# PWR_Supply_With_BUCK_Converter.net
KiCad netlist of a schematic drawn in Altium Designer
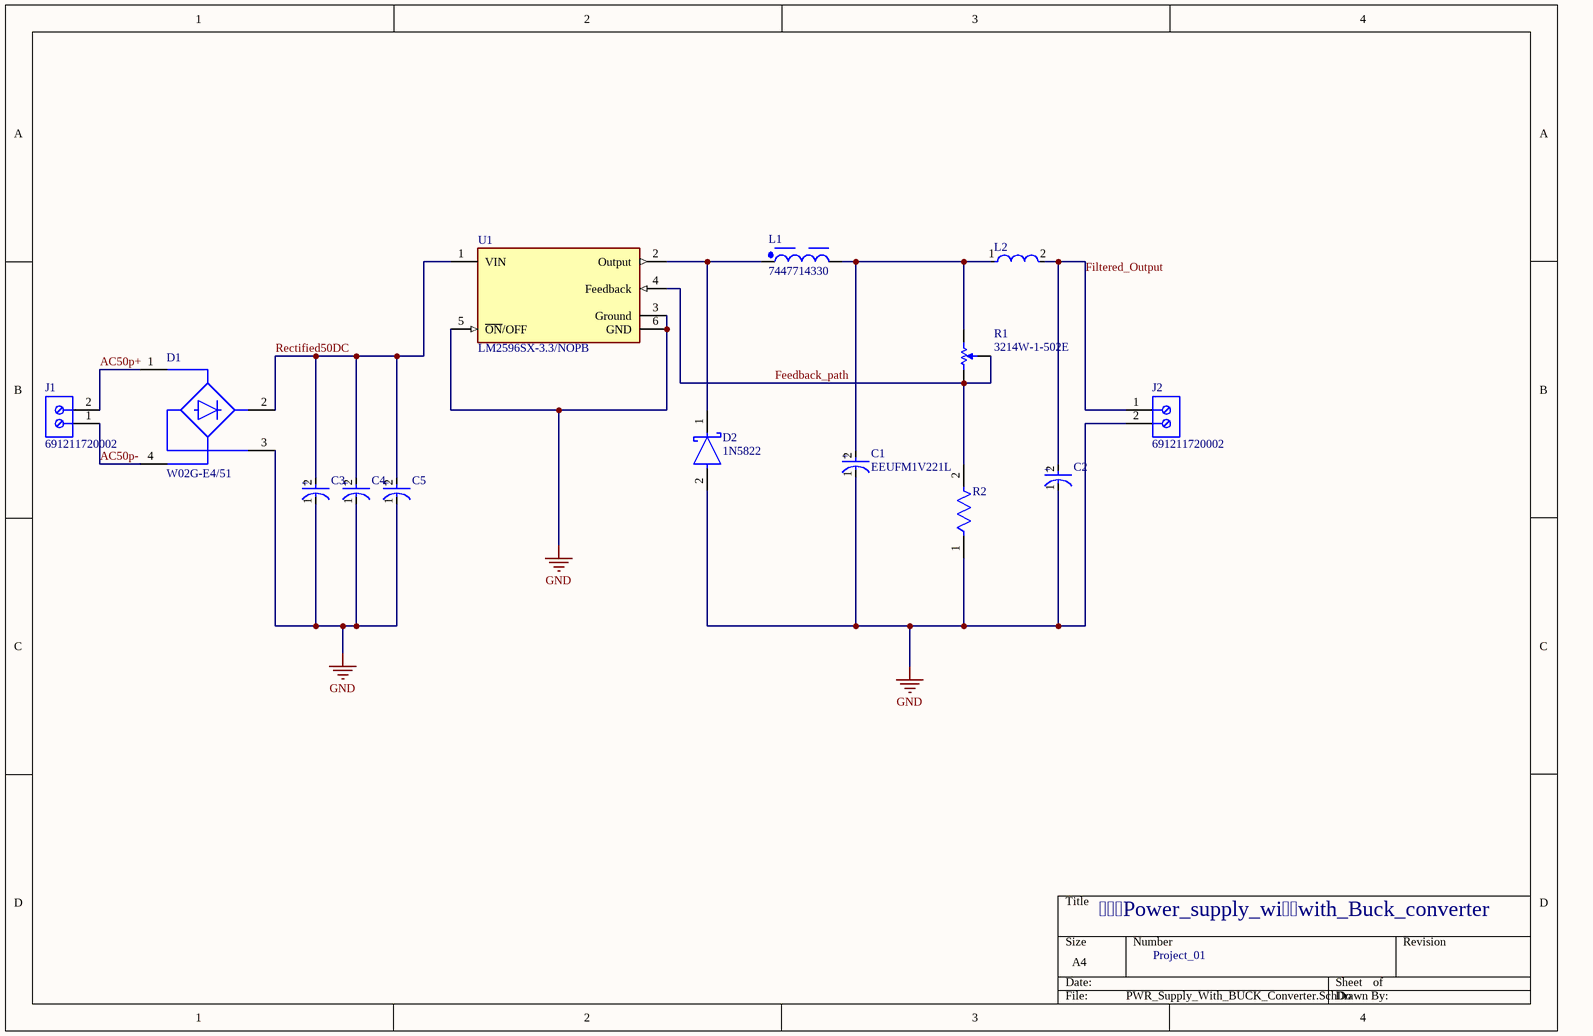
[diagram p0: PWR_Supply_With_BUCK_Converter.SchDoc]

(export (version "E")
  (design (tool "Eeschema 10.0.6"))
  (components
    (comp (ref "C1")
      (value "EEUFM1V221L")
      (footprint "FP-RAD-TH-D_8_0_5-L_15_1-MFG")
      (description "Aluminum Electrolytic Capacitors (Radial Lead Type) 220uF ±20% 35V")
      (fields (field (name "TOLERANCE") "20%") (field (name "VOLTAGE") "35V"))
      (libsource (lib "Altium Content Vault") (part "a00bbbee19879c290e62620ae7e47b1"))
    )
    (comp (ref "C2")
      (value "EEUFR1H101")
      (footprint "FP-RAD-TH-D_8_0_5-L_11_5-MFG")
      (description "Aluminum Electrolytic Capacitors (Radial Lead Type) 100uF ±20% 50V")
      (fields (field (name "VOLTAGE") "50V") (field (name "TOLERANCE") "20%"))
      (libsource (lib "Altium Content Vault") (part "a00bbbee19879c290e62620ae7e47b1"))
    )
    (comp (ref "C3")
      (value "EEUFK0J102L")
      (footprint "FP-RAD-TH-D_8_0_5-L_15_1-MFG")
      (description "Aluminum Electrolytic Capacitors (Radial Lead Type) AEC-Q200 Qualified 1000uF ±20% 6.3V")
      (fields (field (name "VOLTAGE") "6.3V") (field (name "TOLERANCE") "20%"))
      (libsource (lib "Altium Content Vault") (part "a00bbbee19879c290e62620ae7e47b1"))
    )
    (comp (ref "C4")
      (value "EEUFK0J102L")
      (footprint "FP-RAD-TH-D_8_0_5-L_15_1-MFG")
      (description "Aluminum Electrolytic Capacitors (Radial Lead Type) AEC-Q200 Qualified 1000uF ±20% 6.3V")
      (fields (field (name "VOLTAGE") "6.3V") (field (name "TOLERANCE") "20%"))
      (libsource (lib "Altium Content Vault") (part "a00bbbee19879c290e62620ae7e47b1"))
    )
    (comp (ref "C5")
      (value "EEUFR1H101")
      (footprint "FP-RAD-TH-D_8_0_5-L_11_5-MFG")
      (description "Aluminum Electrolytic Capacitors (Radial Lead Type) 100uF ±20% 50V")
      (fields (field (name "VOLTAGE") "50V") (field (name "TOLERANCE") "20%"))
      (libsource (lib "Altium Content Vault") (part "a00bbbee19879c290e62620ae7e47b1"))
    )
    (comp (ref "D1")
      (value "W02G-E4/51")
      (footprint "FP-WOG-MFG")
      (description "BRIDGE RECT 1PHASE 200V 1.5A WOG")
      (libsource (lib "Altium Content Vault") (part "ce9e859d166ef05ab3fd3217f7b9797"))
    )
    (comp (ref "D2")
      (value "1N5822")
      (footprint "FP-DO-201AD-MFG")
      (description "DIODE SCHOTTKY 40V 3A DO201AD")
      (fields
        (field (name "OCTOPART") "https://octopart.com/1n5822-stmicroelectronics-323225")
        (field (name "MANUFACTURER") "STMicroelectronics")
      )
      (libsource (lib "Altium Content Vault") (part "1d6ec82d83fb6aee721767c19dac4b9"))
    )
    (comp (ref "J1")
      (value "691211720002")
      (footprint "691211720002")
      (fields (field (name "VOLTAGE") "300V"))
      (libsource (lib "Altium Content Vault") (part "TBL - 1R - 02P - Screw"))
    )
    (comp (ref "J2")
      (value "691211720002")
      (footprint "691211720002")
      (fields (field (name "VOLTAGE") "300V"))
      (libsource (lib "Altium Content Vault") (part "TBL - 1R - 02P - Screw"))
    )
    (comp (ref "L1")
      (value "7447714330")
      (footprint "WE-PD_1050P")
      (fields (field (name "TOLERANCE") "20%"))
      (libsource (lib "Altium Content Vault") (part "Inductor - 2"))
    )
    (comp (ref "L2")
      (value "IHLP2525CZER220M11")
      (footprint "FP-IHLP-2525CZ-FP_2_413x3-MFG")
      (description "Commercial Inductors, Low DCR Series 22uH 2.9A 135mΩ 20%")
      (fields (field (name "TOLERANCE") "20%"))
      (libsource (lib "Altium Content Vault") (part "725321dda6339637d4d059423bc1c3c"))
    )
    (comp (ref "R1")
      (value "3214W-1-502E")
      (footprint "BOUR-3214W_V")
      (fields (field (name "MANUFACTURER") "Bourns"))
      (libsource (lib "Altium Content Vault") (part "RES-ADJ-3_A"))
    )
    (comp (ref "R2")
      (value "MCA12060D5000BP500")
      (footprint "FP-MCA1206-IPC_C")
      (description "Res MC Precision Thin Film 1206 500Ω 0.1% 0.25W ±25ppm/°C Molded Paper T/R")
      (fields (field (name "TOLERANCE") "0.1%"))
      (libsource (lib "Altium Content Vault") (part "1029c3af85768c4190bb7ad29bc67b5"))
    )
    (comp (ref "U1")
      (value "LM2596SX-3.3/NOPB")
      (footprint "FP-KTT0005B-MFG")
      (description "IC REG BUCK 3.3V 3A TO263-5")
      (libsource (lib "Altium Content Vault") (part "764e866748593119a4ee8b47c98b122"))
    )
  )
  (nets
    (net (code "1") (name "/AC50p+") (class "Default")
      (node (ref "D1") (pin "1") (pinfunction "1_~_1") (pintype "passive"))
      (node (ref "J1") (pin "2") (pinfunction "2_2") (pintype "passive"))
    )
    (net (code "2") (name "/AC50p-") (class "Default")
      (node (ref "D1") (pin "4") (pinfunction "2_~_4") (pintype "passive"))
      (node (ref "J1") (pin "1") (pinfunction "1_1") (pintype "passive"))
    )
    (net (code "3") (name "/Feedback_path") (class "Default")
      (node (ref "R1") (pin "1") (pinfunction "1_1") (pintype "passive"))
      (node (ref "R1") (pin "2") (pinfunction "2_2") (pintype "passive"))
      (node (ref "R2") (pin "2") (pinfunction "2_2") (pintype "passive"))
      (node (ref "U1") (pin "4") (pinfunction "Feedback_4") (pintype "input"))
    )
    (net (code "4") (name "/Filtered_Output") (class "Default")
      (node (ref "C2") (pin "2") (pinfunction "A_2") (pintype "passive"))
      (node (ref "J2") (pin "1") (pinfunction "1_1") (pintype "passive"))
      (node (ref "L2") (pin "2") (pinfunction "2_2") (pintype "passive"))
    )
    (net (code "5") (name "/Rectified50DC") (class "Default")
      (node (ref "C3") (pin "2") (pinfunction "A_2") (pintype "passive"))
      (node (ref "C4") (pin "2") (pinfunction "A_2") (pintype "passive"))
      (node (ref "C5") (pin "2") (pinfunction "A_2") (pintype "passive"))
      (node (ref "D1") (pin "2") (pinfunction "+_2") (pintype "passive"))
      (node (ref "U1") (pin "1") (pinfunction "VIN_1") (pintype "power_in"))
    )
    (net (code "6") (name "GND") (class "Default")
      (node (ref "C1") (pin "1") (pinfunction "C_1") (pintype "passive"))
      (node (ref "C2") (pin "1") (pinfunction "C_1") (pintype "passive"))
      (node (ref "C3") (pin "1") (pinfunction "C_1") (pintype "passive"))
      (node (ref "C4") (pin "1") (pinfunction "C_1") (pintype "passive"))
      (node (ref "C5") (pin "1") (pinfunction "C_1") (pintype "passive"))
      (node (ref "D1") (pin "3") (pinfunction "-_3") (pintype "passive"))
      (node (ref "D2") (pin "2") (pinfunction "A_2") (pintype "passive"))
      (node (ref "J2") (pin "2") (pinfunction "2_2") (pintype "passive"))
      (node (ref "R2") (pin "1") (pinfunction "1_1") (pintype "passive"))
      (node (ref "U1") (pin "3") (pinfunction "Ground_3") (pintype "power_in"))
      (node (ref "U1") (pin "5") (pinfunction "~{ON}/OFF_5") (pintype "input"))
      (node (ref "U1") (pin "6") (pinfunction "GND_6") (pintype "power_in"))
    )
    (net (code "7") (name "Net-(C1-A)") (class "Default")
      (node (ref "C1") (pin "2") (pinfunction "A_2") (pintype "passive"))
      (node (ref "L1") (pin "2") (pinfunction "2_2") (pintype "passive"))
      (node (ref "L2") (pin "1") (pinfunction "1_1") (pintype "passive"))
      (node (ref "R1") (pin "3") (pinfunction "3_3") (pintype "passive"))
    )
    (net (code "8") (name "Net-(D2-C)") (class "Default")
      (node (ref "D2") (pin "1") (pinfunction "C_1") (pintype "passive"))
      (node (ref "L1") (pin "1") (pinfunction "1_1") (pintype "passive"))
      (node (ref "U1") (pin "2") (pinfunction "Output_2") (pintype "output"))
    )
  )
)
